# MCU_Display.net
KiCad netlist of a schematic drawn in Altium Designer
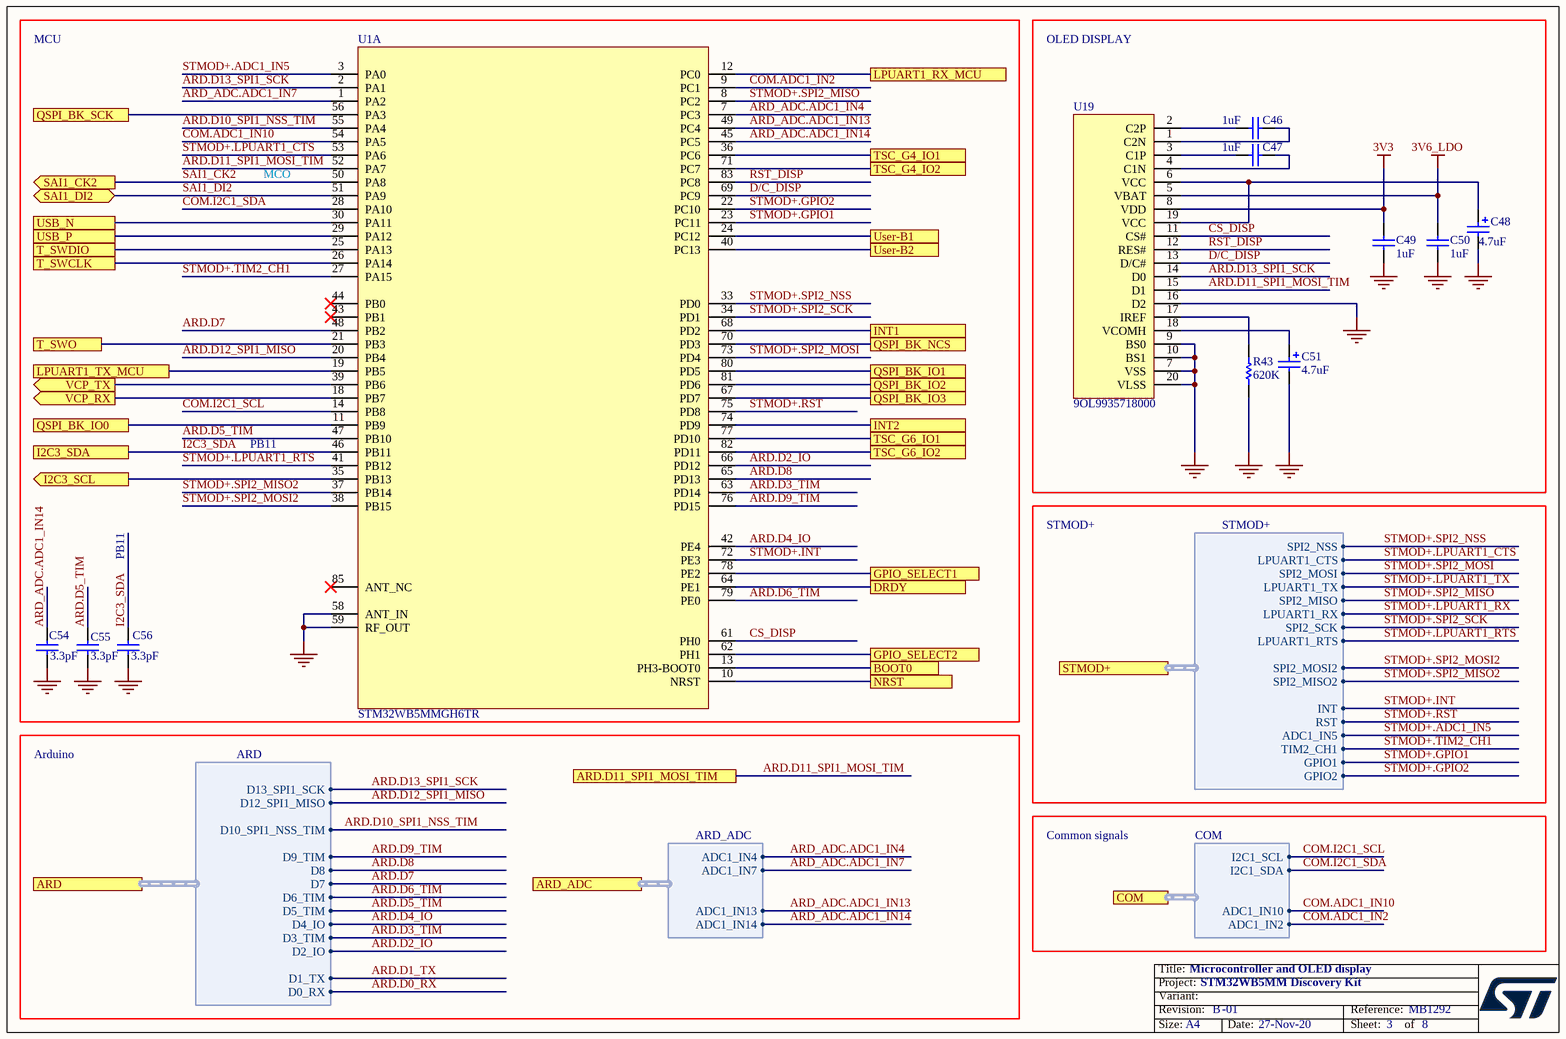
[diagram p0: MCU_Display.SchDoc]

(export (version "E")
  (design (tool "Eeschema 10.0.6"))
  (components
    (comp (ref "C46")
      (value "1uF")
      (footprint "C0603")
      (description "Capacitor, MLCC, 1uF, 16V, X5R, +/-10%, 0603, T=0,8mm")
      (fields
        (field (name "INTERNAL_PART_NUMBER") "MCD-00010")
        (field (name "MANUFACTURER_PART_NUMBER") "CC0603KRX5R7BB105")
      )
      (libsource (lib "MCD_PARTS_database") (part "Capacitor"))
    )
    (comp (ref "C47")
      (value "1uF")
      (footprint "C0603")
      (description "Capacitor, MLCC, 1uF, 16V, X5R, +/-10%, 0603, T=0,8mm")
      (fields
        (field (name "INTERNAL_PART_NUMBER") "MCD-00010")
        (field (name "MANUFACTURER_PART_NUMBER") "CC0603KRX5R7BB105")
      )
      (libsource (lib "MCD_PARTS_database") (part "Capacitor"))
    )
    (comp (ref "C48")
      (value "4.7uF")
      (footprint "CPOL_TAJ-A_1206_H180")
      (description "Capacitor, Tantalum, 4.7uF, 25V, 5.5ohms, 10%,pkg Type_A (3216 metric), T=1.6mm")
      (fields
        (field (name "INTERNAL_PART_NUMBER") "MCD-01043")
        (field (name "MANUFACTURER_PART_NUMBER") "293D475X9025A2TE3")
      )
      (libsource (lib "MCD_PARTS_database") (part "Cap_POL_TANA"))
    )
    (comp (ref "C49")
      (value "1uF")
      (footprint "C0603")
      (description "Capacitor, MLCC, 1uF, 16V, X5R, +/-10%, 0603, T=0,8mm")
      (fields
        (field (name "INTERNAL_PART_NUMBER") "MCD-00010")
        (field (name "MANUFACTURER_PART_NUMBER") "CC0603KRX5R7BB105")
      )
      (libsource (lib "MCD_PARTS_database") (part "Capacitor"))
    )
    (comp (ref "C50")
      (value "1uF")
      (footprint "C0603")
      (description "Capacitor, MLCC, 1uF, 16V, X5R, +/-10%, 0603, T=0,8mm")
      (fields
        (field (name "INTERNAL_PART_NUMBER") "MCD-00010")
        (field (name "MANUFACTURER_PART_NUMBER") "CC0603KRX5R7BB105")
      )
      (libsource (lib "MCD_PARTS_database") (part "Capacitor"))
    )
    (comp (ref "C51")
      (value "4.7uF")
      (footprint "CPOL_TAJ-A_1206_H180")
      (description "Capacitor, Tantalum, 4.7uF, 25V, 5.5ohms, 10%,pkg Type_A (3216 metric), T=1.6mm")
      (fields
        (field (name "INTERNAL_PART_NUMBER") "MCD-01043")
        (field (name "MANUFACTURER_PART_NUMBER") "293D475X9025A2TE3")
      )
      (libsource (lib "MCD_PARTS_database") (part "Cap_POL_TANA"))
    )
    (comp (ref "C54")
      (value "3.3pF")
      (footprint "C0201_H0P3")
      (description "Capacitor, MLCC, 3.3pF, 50V, NPO, +-0.05pF, 0201, T=0.3mm\".")
      (fields (field (name "INTERNAL_PART_NUMBER") "MCD-02284") (field (name "MANUFACTURER") "MURATA"))
      (libsource (lib "MCD_PARTS_database") (part "Capacitor"))
    )
    (comp (ref "C55")
      (value "3.3pF")
      (footprint "C0201_H0P3")
      (description "Capacitor, MLCC, 3.3pF, 50V, NPO, +-0.05pF, 0201, T=0.3mm\".")
      (fields (field (name "INTERNAL_PART_NUMBER") "MCD-02284") (field (name "MANUFACTURER") "MURATA"))
      (libsource (lib "MCD_PARTS_database") (part "Capacitor"))
    )
    (comp (ref "C56")
      (value "3.3pF")
      (footprint "C0201_H0P3")
      (description "Capacitor, MLCC, 3.3pF, 50V, NPO, +-0.05pF, 0201, T=0.3mm\".")
      (fields (field (name "INTERNAL_PART_NUMBER") "MCD-02284") (field (name "MANUFACTURER") "MURATA"))
      (libsource (lib "MCD_PARTS_database") (part "Capacitor"))
    )
    (comp (ref "R43")
      (value "620K")
      (footprint "R0603")
      (description "Resistor,620K,0603,1%,1/10W")
      (fields
        (field (name "INTERNAL_PART_NUMBER") "MCD-00506")
        (field (name "MANUFACTURER_PART_NUMBER") "RC0603FR-07620KL")
      )
      (libsource (lib "MCD_PARTS_database") (part "Resistor"))
    )
    (comp (ref "U1")
      (value "STM32WB5MMGH6TR")
      (footprint "MOD_DORY_STM_86P_7P3X11_H1P342")
      (description "STM32 BLE module based on STM32WB55")
      (fields
        (field (name "INTERNAL_PART_NUMBER") "MCD-01965")
        (field (name "MANUFACTURER") "STMICROELECTRONICS")
      )
      (libsource (lib "MCD_PARTS_database") (part "STM32WB5MMGH6TR"))
    )
    (comp (ref "U19")
      (value "9OL9935718000")
      (footprint "OLED_RITDISPLAY_9OL9935718000")
      (description "128*64 Dots 20-pin OLED display")
      (fields (field (name "INTERNAL_PART_NUMBER") "MCD-01925") (field (name "MANUFACTURER") "RITDISPLAY"))
      (libsource (lib "MCD_PARTS_database") (part "OLED_RITDISPLAY_9OL9935718000"))
    )
  )
  (nets
    (net (code "7") (name "/ARD.D2_IO") (class "Default")
      (node (ref "U1") (pin "66") (pinfunction "PD12_66") (pintype "passive"))
    )
    (net (code "8") (name "/ARD.D3_TIM") (class "Default")
      (node (ref "U1") (pin "63") (pinfunction "PD14_63") (pintype "passive"))
    )
    (net (code "9") (name "/ARD.D4_IO") (class "Default")
      (node (ref "U1") (pin "42") (pinfunction "PE4_42") (pintype "passive"))
    )
    (net (code "10") (name "/ARD.D5_TIM") (class "Default")
      (node (ref "C55") (pin "2") (pinfunction "2_2") (pintype "passive"))
      (node (ref "U1") (pin "47") (pinfunction "PB10_47") (pintype "passive"))
    )
    (net (code "11") (name "/ARD.D6_TIM") (class "Default")
      (node (ref "U1") (pin "79") (pinfunction "PE0_79") (pintype "passive"))
    )
    (net (code "12") (name "/ARD.D7") (class "Default")
      (node (ref "U1") (pin "48") (pinfunction "PB2_48") (pintype "passive"))
    )
    (net (code "13") (name "/ARD.D8") (class "Default")
      (node (ref "U1") (pin "65") (pinfunction "PD13_65") (pintype "passive"))
    )
    (net (code "14") (name "/ARD.D9_TIM") (class "Default")
      (node (ref "U1") (pin "76") (pinfunction "PD15_76") (pintype "passive"))
    )
    (net (code "15") (name "/ARD.D10_SPI1_NSS_TIM") (class "Default")
      (node (ref "U1") (pin "55") (pinfunction "PA4_55") (pintype "passive"))
    )
    (net (code "16") (name "/ARD.D11_SPI1_MOSI_TIM") (class "Default")
      (node (ref "U1") (pin "52") (pinfunction "PA7_52") (pintype "passive"))
      (node (ref "U19") (pin "15") (pinfunction "D1_15") (pintype "passive"))
    )
    (net (code "17") (name "/ARD.D12_SPI1_MISO") (class "Default")
      (node (ref "U1") (pin "20") (pinfunction "PB4_20") (pintype "passive"))
    )
    (net (code "18") (name "/ARD.D13_SPI1_SCK") (class "Default")
      (node (ref "U1") (pin "2") (pinfunction "PA1_2") (pintype "passive"))
      (node (ref "U19") (pin "14") (pinfunction "D0_14") (pintype "passive"))
    )
    (net (code "19") (name "/ARD_ADC.ADC1_IN4") (class "Default")
      (node (ref "U1") (pin "7") (pinfunction "PC3_7") (pintype "passive"))
    )
    (net (code "20") (name "/ARD_ADC.ADC1_IN7") (class "Default")
      (node (ref "U1") (pin "1") (pinfunction "PA2_1") (pintype "passive"))
    )
    (net (code "21") (name "/ARD_ADC.ADC1_IN13") (class "Default")
      (node (ref "U1") (pin "49") (pinfunction "PC4_49") (pintype "passive"))
    )
    (net (code "22") (name "/ARD_ADC.ADC1_IN14") (class "Default")
      (node (ref "C54") (pin "1") (pinfunction "1_1") (pintype "passive"))
      (node (ref "U1") (pin "45") (pinfunction "PC5_45") (pintype "passive"))
    )
    (net (code "23") (name "/BOOT0") (class "Default")
      (node (ref "U1") (pin "13") (pinfunction "PH3-BOOT0_13") (pintype "passive"))
    )
    (net (code "24") (name "/COM.ADC1_IN2") (class "Default")
      (node (ref "U1") (pin "9") (pinfunction "PC1_9") (pintype "passive"))
    )
    (net (code "25") (name "/COM.ADC1_IN10") (class "Default")
      (node (ref "U1") (pin "54") (pinfunction "PA5_54") (pintype "passive"))
    )
    (net (code "26") (name "/COM.I2C1_SCL") (class "Default")
      (node (ref "U1") (pin "14") (pinfunction "PB8_14") (pintype "passive"))
    )
    (net (code "27") (name "/COM.I2C1_SDA") (class "Default")
      (node (ref "U1") (pin "28") (pinfunction "PA10_28") (pintype "passive"))
    )
    (net (code "28") (name "/CS_DISP") (class "Default")
      (node (ref "U1") (pin "61") (pinfunction "PH0_61") (pintype "passive"))
      (node (ref "U19") (pin "11") (pinfunction "CS#_11") (pintype "passive"))
    )
    (net (code "29") (name "/DRDY") (class "Default")
      (node (ref "U1") (pin "64") (pinfunction "PE1_64") (pintype "passive"))
    )
    (net (code "30") (name "/D{slash}C_DISP") (class "Default")
      (node (ref "U1") (pin "69") (pinfunction "PC9_69") (pintype "passive"))
      (node (ref "U19") (pin "13") (pinfunction "D/C#_13") (pintype "passive"))
    )
    (net (code "31") (name "/GPIO_SELECT1") (class "Default")
      (node (ref "U1") (pin "78") (pinfunction "PE2_78") (pintype "passive"))
    )
    (net (code "32") (name "/GPIO_SELECT2") (class "Default")
      (node (ref "U1") (pin "62") (pinfunction "PH1_62") (pintype "passive"))
    )
    (net (code "33") (name "/I2C3_SCL") (class "Default")
      (node (ref "U1") (pin "35") (pinfunction "PB13_35") (pintype "passive"))
    )
    (net (code "34") (name "/I2C3_SDA") (class "Default")
      (node (ref "C56") (pin "2") (pinfunction "2_2") (pintype "passive"))
      (node (ref "U1") (pin "46") (pinfunction "PB11_46") (pintype "passive"))
    )
    (net (code "35") (name "/INT1") (class "Default")
      (node (ref "U1") (pin "68") (pinfunction "PD2_68") (pintype "passive"))
    )
    (net (code "36") (name "/INT2") (class "Default")
      (node (ref "U1") (pin "74") (pinfunction "PD9_74") (pintype "passive"))
    )
    (net (code "37") (name "/LPUART1_RX_MCU") (class "Default")
      (node (ref "U1") (pin "12") (pinfunction "PC0_12") (pintype "passive"))
    )
    (net (code "38") (name "/LPUART1_TX_MCU") (class "Default")
      (node (ref "U1") (pin "19") (pinfunction "PB5_19") (pintype "passive"))
    )
    (net (code "39") (name "/NRST") (class "Default")
      (node (ref "U1") (pin "10") (pinfunction "NRST_10") (pintype "passive"))
    )
    (net (code "40") (name "/QSPI_BK_IO0") (class "Default")
      (node (ref "U1") (pin "11") (pinfunction "PB9_11") (pintype "passive"))
    )
    (net (code "41") (name "/QSPI_BK_IO1") (class "Default")
      (node (ref "U1") (pin "80") (pinfunction "PD5_80") (pintype "passive"))
    )
    (net (code "42") (name "/QSPI_BK_IO2") (class "Default")
      (node (ref "U1") (pin "81") (pinfunction "PD6_81") (pintype "passive"))
    )
    (net (code "43") (name "/QSPI_BK_IO3") (class "Default")
      (node (ref "U1") (pin "67") (pinfunction "PD7_67") (pintype "passive"))
    )
    (net (code "44") (name "/QSPI_BK_NCS") (class "Default")
      (node (ref "U1") (pin "70") (pinfunction "PD3_70") (pintype "passive"))
    )
    (net (code "45") (name "/QSPI_BK_SCK") (class "Default")
      (node (ref "U1") (pin "56") (pinfunction "PA3_56") (pintype "passive"))
    )
    (net (code "46") (name "/RST_DISP") (class "Default")
      (node (ref "U1") (pin "83") (pinfunction "PC8_83") (pintype "passive"))
      (node (ref "U19") (pin "12") (pinfunction "RES#_12") (pintype "passive"))
    )
    (net (code "47") (name "/SAI1_CK2") (class "Default")
      (node (ref "U1") (pin "50") (pinfunction "PA8_50") (pintype "passive"))
    )
    (net (code "48") (name "/SAI1_DI2") (class "Default")
      (node (ref "U1") (pin "51") (pinfunction "PA9_51") (pintype "passive"))
    )
    (net (code "49") (name "/STMOD+.ADC1_IN5") (class "Default")
      (node (ref "U1") (pin "3") (pinfunction "PA0_3") (pintype "passive"))
    )
    (net (code "50") (name "/STMOD+.GPIO1") (class "Default")
      (node (ref "U1") (pin "23") (pinfunction "PC11_23") (pintype "passive"))
    )
    (net (code "51") (name "/STMOD+.GPIO2") (class "Default")
      (node (ref "U1") (pin "22") (pinfunction "PC10_22") (pintype "passive"))
    )
    (net (code "52") (name "/STMOD+.INT") (class "Default")
      (node (ref "U1") (pin "72") (pinfunction "PE3_72") (pintype "passive"))
    )
    (net (code "53") (name "/STMOD+.LPUART1_CTS") (class "Default")
      (node (ref "U1") (pin "53") (pinfunction "PA6_53") (pintype "passive"))
    )
    (net (code "54") (name "/STMOD+.LPUART1_RTS") (class "Default")
      (node (ref "U1") (pin "41") (pinfunction "PB12_41") (pintype "passive"))
    )
    (net (code "57") (name "/STMOD+.RST") (class "Default")
      (node (ref "U1") (pin "75") (pinfunction "PD8_75") (pintype "passive"))
    )
    (net (code "58") (name "/STMOD+.SPI2_MISO") (class "Default")
      (node (ref "U1") (pin "8") (pinfunction "PC2_8") (pintype "passive"))
    )
    (net (code "59") (name "/STMOD+.SPI2_MISO2") (class "Default")
      (node (ref "U1") (pin "37") (pinfunction "PB14_37") (pintype "passive"))
    )
    (net (code "60") (name "/STMOD+.SPI2_MOSI") (class "Default")
      (node (ref "U1") (pin "73") (pinfunction "PD4_73") (pintype "passive"))
    )
    (net (code "61") (name "/STMOD+.SPI2_MOSI2") (class "Default")
      (node (ref "U1") (pin "38") (pinfunction "PB15_38") (pintype "passive"))
    )
    (net (code "62") (name "/STMOD+.SPI2_NSS") (class "Default")
      (node (ref "U1") (pin "33") (pinfunction "PD0_33") (pintype "passive"))
    )
    (net (code "63") (name "/STMOD+.SPI2_SCK") (class "Default")
      (node (ref "U1") (pin "34") (pinfunction "PD1_34") (pintype "passive"))
    )
    (net (code "64") (name "/STMOD+.TIM2_CH1") (class "Default")
      (node (ref "U1") (pin "27") (pinfunction "PA15_27") (pintype "passive"))
    )
    (net (code "65") (name "/TSC_G4_IO1") (class "Default")
      (node (ref "U1") (pin "36") (pinfunction "PC6_36") (pintype "passive"))
    )
    (net (code "66") (name "/TSC_G4_IO2") (class "Default")
      (node (ref "U1") (pin "71") (pinfunction "PC7_71") (pintype "passive"))
    )
    (net (code "67") (name "/TSC_G6_IO1") (class "Default")
      (node (ref "U1") (pin "77") (pinfunction "PD10_77") (pintype "passive"))
    )
    (net (code "68") (name "/TSC_G6_IO2") (class "Default")
      (node (ref "U1") (pin "82") (pinfunction "PD11_82") (pintype "passive"))
    )
    (net (code "69") (name "/T_SWCLK") (class "Default")
      (node (ref "U1") (pin "26") (pinfunction "PA14_26") (pintype "passive"))
    )
    (net (code "70") (name "/T_SWDIO") (class "Default")
      (node (ref "U1") (pin "25") (pinfunction "PA13_25") (pintype "passive"))
    )
    (net (code "71") (name "/T_SWO") (class "Default")
      (node (ref "U1") (pin "21") (pinfunction "PB3_21") (pintype "passive"))
    )
    (net (code "72") (name "/USB_N") (class "Default")
      (node (ref "U1") (pin "30") (pinfunction "PA11_30") (pintype "passive"))
    )
    (net (code "73") (name "/USB_P") (class "Default")
      (node (ref "U1") (pin "29") (pinfunction "PA12_29") (pintype "passive"))
    )
    (net (code "74") (name "/User-B1") (class "Default")
      (node (ref "U1") (pin "24") (pinfunction "PC12_24") (pintype "passive"))
    )
    (net (code "75") (name "/User-B2") (class "Default")
      (node (ref "U1") (pin "40") (pinfunction "PC13_40") (pintype "passive"))
    )
    (net (code "76") (name "/VCP_RX") (class "Default")
      (node (ref "U1") (pin "18") (pinfunction "PB7_18") (pintype "passive"))
    )
    (net (code "77") (name "/VCP_TX") (class "Default")
      (node (ref "U1") (pin "39") (pinfunction "PB6_39") (pintype "passive"))
    )
    (net (code "82") (name "3V3") (class "Default")
      (node (ref "C49") (pin "1") (pinfunction "1_1") (pintype "passive"))
      (node (ref "U19") (pin "8") (pinfunction "VDD_8") (pintype "passive"))
    )
    (net (code "83") (name "3V6_LDO") (class "Default")
      (node (ref "C50") (pin "1") (pinfunction "1_1") (pintype "passive"))
      (node (ref "U19") (pin "5") (pinfunction "VBAT_5") (pintype "passive"))
    )
    (net (code "84") (name "GND") (class "Default")
      (node (ref "C48") (pin "2") (pinfunction "2_2") (pintype "passive"))
      (node (ref "C49") (pin "2") (pinfunction "2_2") (pintype "passive"))
      (node (ref "C50") (pin "2") (pinfunction "2_2") (pintype "passive"))
      (node (ref "C51") (pin "2") (pinfunction "2_2") (pintype "passive"))
      (node (ref "C54") (pin "2") (pinfunction "2_2") (pintype "passive"))
      (node (ref "C55") (pin "1") (pinfunction "1_1") (pintype "passive"))
      (node (ref "C56") (pin "1") (pinfunction "1_1") (pintype "passive"))
      (node (ref "R43") (pin "1") (pinfunction "1_1") (pintype "passive"))
      (node (ref "U1") (pin "58") (pinfunction "ANT_IN_58") (pintype "passive"))
      (node (ref "U1") (pin "59") (pinfunction "RF_OUT_59") (pintype "passive"))
      (node (ref "U19") (pin "10") (pinfunction "BS1_10") (pintype "passive"))
      (node (ref "U19") (pin "16") (pinfunction "D2_16") (pintype "passive"))
      (node (ref "U19") (pin "20") (pinfunction "VLSS_20") (pintype "passive"))
      (node (ref "U19") (pin "7") (pinfunction "VSS_7") (pintype "passive"))
      (node (ref "U19") (pin "9") (pinfunction "BS0_9") (pintype "passive"))
    )
    (net (code "85") (name "Net-(C48-Pad1)") (class "Default")
      (node (ref "C48") (pin "1") (pinfunction "1_1") (pintype "passive"))
      (node (ref "U19") (pin "19") (pinfunction "VCC_19") (pintype "passive"))
      (node (ref "U19") (pin "6") (pinfunction "VCC_6") (pintype "passive"))
    )
    (net (code "86") (name "Net-(U19-C1N)") (class "Default")
      (node (ref "C47") (pin "2") (pinfunction "2_2") (pintype "passive"))
      (node (ref "U19") (pin "4") (pinfunction "C1N_4") (pintype "passive"))
    )
    (net (code "87") (name "Net-(U19-C1P)") (class "Default")
      (node (ref "C47") (pin "1") (pinfunction "1_1") (pintype "passive"))
      (node (ref "U19") (pin "3") (pinfunction "C1P_3") (pintype "passive"))
    )
    (net (code "88") (name "Net-(U19-C2N)") (class "Default")
      (node (ref "C46") (pin "2") (pinfunction "2_2") (pintype "passive"))
      (node (ref "U19") (pin "1") (pinfunction "C2N_1") (pintype "passive"))
    )
    (net (code "89") (name "Net-(U19-C2P)") (class "Default")
      (node (ref "C46") (pin "1") (pinfunction "1_1") (pintype "passive"))
      (node (ref "U19") (pin "2") (pinfunction "C2P_2") (pintype "passive"))
    )
    (net (code "90") (name "Net-(U19-IREF)") (class "Default")
      (node (ref "R43") (pin "2") (pinfunction "2_2") (pintype "passive"))
      (node (ref "U19") (pin "17") (pinfunction "IREF_17") (pintype "passive"))
    )
    (net (code "91") (name "Net-(U19-VCOMH)") (class "Default")
      (node (ref "C51") (pin "1") (pinfunction "1_1") (pintype "passive"))
      (node (ref "U19") (pin "18") (pinfunction "VCOMH_18") (pintype "passive"))
    )
    (net (code "92") (name "unconnected-(U1A-ANT_NC-Pad85)") (class "Default")
      (node (ref "U1") (pin "85") (pinfunction "ANT_NC_85") (pintype "passive+no_connect"))
    )
    (net (code "93") (name "unconnected-(U1A-PB0-Pad44)") (class "Default")
      (node (ref "U1") (pin "44") (pinfunction "PB0_44") (pintype "passive+no_connect"))
    )
    (net (code "94") (name "unconnected-(U1A-PB1-Pad43)") (class "Default")
      (node (ref "U1") (pin "43") (pinfunction "PB1_43") (pintype "passive+no_connect"))
    )
  )
)
